# XOR_GATE.net
KiCad netlist of a schematic drawn in Altium Designer
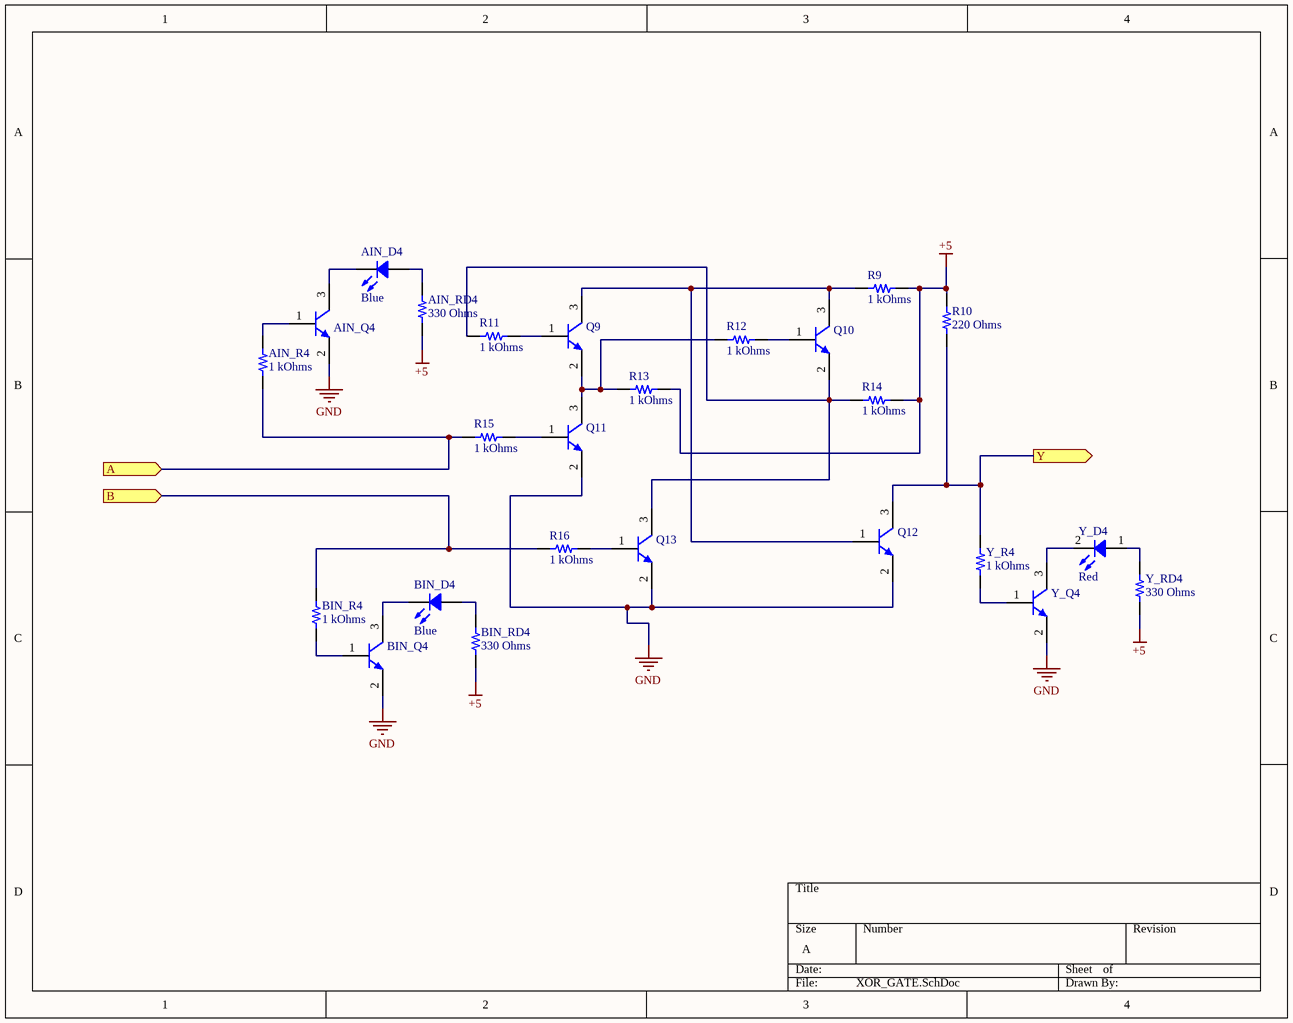
[diagram p0: XOR_GATE.SchDoc]

(export (version "E")
  (design (tool "Eeschema 10.0.6"))
  (components
    (comp (ref "AIN_D4")
      (value "Blue")
      (footprint "LED 0603_1608 BLUE")
      (description "LED BLUE CLEAR 0603 SMD")
      (fields (field (name "PART NUMBER") "IN-S63AT5B") (field (name "MANUFACTURER") "Inolux"))
      (libsource (lib "Celestial Altium Library - altium_library") (part "LED"))
    )
    (comp (ref "AIN_Q4")
      (value "MMSS8050-L-TP")
      (footprint "MCCSEMI SOT-23-3")
      (description "TRANS NPN 25V 1.5A SOT23")
      (fields (field (name "MANUFACTURER") "Micro Commercial Co"))
      (libsource (lib "Celestial Altium Library - altium_library") (part "MCCSEMI NPN SOT-23-3"))
    )
    (comp (ref "AIN_R4")
      (value "1 kOhms")
      (footprint "RES 0603_1608")
      (description "RES SMD 1K OHM 0.1% 1/16W 0603")
      (fields
        (field (name "PART NUMBER") "CPF0603B1K0E")
        (field (name "MANUFACTURER") "TE Connectivity Passive Product")
      )
      (libsource (lib "Celestial Altium Library - altium_library") (part "Resistor"))
    )
    (comp (ref "AIN_RD4")
      (value "330 Ohms")
      (footprint "RES 0603_1608")
      (description "RES 330 OHM 5% 1/10W 0603")
      (fields
        (field (name "PART NUMBER") "RMCF0603JT330R")
        (field (name "MANUFACTURER") "Stackpole Electronics Inc")
      )
      (libsource (lib "Celestial Altium Library - altium_library") (part "Resistor"))
    )
    (comp (ref "BIN_D4")
      (value "Blue")
      (footprint "LED 0603_1608 BLUE")
      (description "LED BLUE CLEAR 0603 SMD")
      (fields (field (name "PART NUMBER") "IN-S63AT5B") (field (name "MANUFACTURER") "Inolux"))
      (libsource (lib "Celestial Altium Library - altium_library") (part "LED"))
    )
    (comp (ref "BIN_Q4")
      (value "MMSS8050-L-TP")
      (footprint "MCCSEMI SOT-23-3")
      (description "TRANS NPN 25V 1.5A SOT23")
      (fields (field (name "MANUFACTURER") "Micro Commercial Co"))
      (libsource (lib "Celestial Altium Library - altium_library") (part "MCCSEMI NPN SOT-23-3"))
    )
    (comp (ref "BIN_R4")
      (value "1 kOhms")
      (footprint "RES 0603_1608")
      (description "RES SMD 1K OHM 0.1% 1/16W 0603")
      (fields
        (field (name "PART NUMBER") "CPF0603B1K0E")
        (field (name "MANUFACTURER") "TE Connectivity Passive Product")
      )
      (libsource (lib "Celestial Altium Library - altium_library") (part "Resistor"))
    )
    (comp (ref "BIN_RD4")
      (value "330 Ohms")
      (footprint "RES 0603_1608")
      (description "RES 330 OHM 5% 1/10W 0603")
      (fields
        (field (name "PART NUMBER") "RMCF0603JT330R")
        (field (name "MANUFACTURER") "Stackpole Electronics Inc")
      )
      (libsource (lib "Celestial Altium Library - altium_library") (part "Resistor"))
    )
    (comp (ref "Q9")
      (value "MMSS8050-L-TP")
      (footprint "MCCSEMI SOT-23-3")
      (description "TRANS NPN 25V 1.5A SOT23")
      (fields (field (name "MANUFACTURER") "Micro Commercial Co"))
      (libsource (lib "Celestial Altium Library - altium_library") (part "MCCSEMI NPN SOT-23-3"))
    )
    (comp (ref "Q10")
      (value "MMSS8050-L-TP")
      (footprint "MCCSEMI SOT-23-3")
      (description "TRANS NPN 25V 1.5A SOT23")
      (fields (field (name "MANUFACTURER") "Micro Commercial Co"))
      (libsource (lib "Celestial Altium Library - altium_library") (part "MCCSEMI NPN SOT-23-3"))
    )
    (comp (ref "Q11")
      (value "MMSS8050-L-TP")
      (footprint "MCCSEMI SOT-23-3")
      (description "TRANS NPN 25V 1.5A SOT23")
      (fields (field (name "MANUFACTURER") "Micro Commercial Co"))
      (libsource (lib "Celestial Altium Library - altium_library") (part "MCCSEMI NPN SOT-23-3"))
    )
    (comp (ref "Q12")
      (value "MMSS8050-L-TP")
      (footprint "MCCSEMI SOT-23-3")
      (description "TRANS NPN 25V 1.5A SOT23")
      (fields (field (name "MANUFACTURER") "Micro Commercial Co"))
      (libsource (lib "Celestial Altium Library - altium_library") (part "MCCSEMI NPN SOT-23-3"))
    )
    (comp (ref "Q13")
      (value "MMSS8050-L-TP")
      (footprint "MCCSEMI SOT-23-3")
      (description "TRANS NPN 25V 1.5A SOT23")
      (fields (field (name "MANUFACTURER") "Micro Commercial Co"))
      (libsource (lib "Celestial Altium Library - altium_library") (part "MCCSEMI NPN SOT-23-3"))
    )
    (comp (ref "R9")
      (value "1 kOhms")
      (footprint "RES 0603_1608")
      (description "RES SMD 1K OHM 0.1% 1/16W 0603")
      (fields
        (field (name "PART NUMBER") "CPF0603B1K0E")
        (field (name "MANUFACTURER") "TE Connectivity Passive Product")
      )
      (libsource (lib "Celestial Altium Library - altium_library") (part "Resistor"))
    )
    (comp (ref "R10")
      (value "220 Ohms")
      (footprint "RES 0603_1608")
      (description "RES SMD 220 OHM 0.5% 1/10W 0603")
      (fields
        (field (name "PART NUMBER") "ERA-3AED221V")
        (field (name "MANUFACTURER") "Panasonic Electronic Components")
      )
      (libsource (lib "Celestial Altium Library - altium_library") (part "Resistor"))
    )
    (comp (ref "R11")
      (value "1 kOhms")
      (footprint "RES 0603_1608")
      (description "RES SMD 1K OHM 0.1% 1/16W 0603")
      (fields
        (field (name "PART NUMBER") "CPF0603B1K0E")
        (field (name "MANUFACTURER") "TE Connectivity Passive Product")
      )
      (libsource (lib "Celestial Altium Library - altium_library") (part "Resistor"))
    )
    (comp (ref "R12")
      (value "1 kOhms")
      (footprint "RES 0603_1608")
      (description "RES SMD 1K OHM 0.1% 1/16W 0603")
      (fields
        (field (name "PART NUMBER") "CPF0603B1K0E")
        (field (name "MANUFACTURER") "TE Connectivity Passive Product")
      )
      (libsource (lib "Celestial Altium Library - altium_library") (part "Resistor"))
    )
    (comp (ref "R13")
      (value "1 kOhms")
      (footprint "RES 0603_1608")
      (description "RES SMD 1K OHM 0.1% 1/16W 0603")
      (fields
        (field (name "PART NUMBER") "CPF0603B1K0E")
        (field (name "MANUFACTURER") "TE Connectivity Passive Product")
      )
      (libsource (lib "Celestial Altium Library - altium_library") (part "Resistor"))
    )
    (comp (ref "R14")
      (value "1 kOhms")
      (footprint "RES 0603_1608")
      (description "RES SMD 1K OHM 0.1% 1/16W 0603")
      (fields
        (field (name "PART NUMBER") "CPF0603B1K0E")
        (field (name "MANUFACTURER") "TE Connectivity Passive Product")
      )
      (libsource (lib "Celestial Altium Library - altium_library") (part "Resistor"))
    )
    (comp (ref "R15")
      (value "1 kOhms")
      (footprint "RES 0603_1608")
      (description "RES SMD 1K OHM 0.1% 1/16W 0603")
      (fields
        (field (name "PART NUMBER") "CPF0603B1K0E")
        (field (name "MANUFACTURER") "TE Connectivity Passive Product")
      )
      (libsource (lib "Celestial Altium Library - altium_library") (part "Resistor"))
    )
    (comp (ref "R16")
      (value "1 kOhms")
      (footprint "RES 0603_1608")
      (description "RES SMD 1K OHM 0.1% 1/16W 0603")
      (fields
        (field (name "PART NUMBER") "CPF0603B1K0E")
        (field (name "MANUFACTURER") "TE Connectivity Passive Product")
      )
      (libsource (lib "Celestial Altium Library - altium_library") (part "Resistor"))
    )
    (comp (ref "Y_D4")
      (value "Red")
      (footprint "LED 0603_1608 RED")
      (description "LED RED CLEAR CHIP SMD")
      (fields (field (name "PART NUMBER") "XZMDK53W-8") (field (name "MANUFACTURER") "SunLED"))
      (libsource (lib "") (part "LED_1"))
    )
    (comp (ref "Y_Q4")
      (value "MMSS8050-L-TP")
      (footprint "MCCSEMI SOT-23-3")
      (description "TRANS NPN 25V 1.5A SOT23")
      (fields (field (name "MANUFACTURER") "Micro Commercial Co"))
      (libsource (lib "Celestial Altium Library - altium_library") (part "MCCSEMI NPN SOT-23-3"))
    )
    (comp (ref "Y_R4")
      (value "1 kOhms")
      (footprint "RES 0603_1608")
      (description "RES SMD 1K OHM 0.1% 1/16W 0603")
      (fields
        (field (name "PART NUMBER") "CPF0603B1K0E")
        (field (name "MANUFACTURER") "TE Connectivity Passive Product")
      )
      (libsource (lib "Celestial Altium Library - altium_library") (part "Resistor"))
    )
    (comp (ref "Y_RD4")
      (value "330 Ohms")
      (footprint "RES 0603_1608")
      (description "RES 330 OHM 5% 1/10W 0603")
      (fields
        (field (name "PART NUMBER") "RMCF0603JT330R")
        (field (name "MANUFACTURER") "Stackpole Electronics Inc")
      )
      (libsource (lib "Celestial Altium Library - altium_library") (part "Resistor"))
    )
  )
  (nets
    (net (code "1") (name "+5") (class "Default")
      (node (ref "AIN_RD4") (pin "1") (pinfunction "1_1") (pintype "passive"))
      (node (ref "BIN_RD4") (pin "1") (pinfunction "1_1") (pintype "passive"))
      (node (ref "R10") (pin "2") (pinfunction "2_2") (pintype "passive"))
      (node (ref "R13") (pin "2") (pinfunction "2_2") (pintype "passive"))
      (node (ref "R14") (pin "2") (pinfunction "2_2") (pintype "passive"))
      (node (ref "R9") (pin "2") (pinfunction "2_2") (pintype "passive"))
      (node (ref "Y_RD4") (pin "1") (pinfunction "1_1") (pintype "passive"))
    )
    (net (code "2") (name "/A") (class "Default")
      (node (ref "AIN_R4") (pin "2") (pinfunction "2_2") (pintype "passive"))
      (node (ref "R15") (pin "1") (pinfunction "1_1") (pintype "passive"))
    )
    (net (code "3") (name "/B") (class "Default")
      (node (ref "BIN_R4") (pin "2") (pinfunction "2_2") (pintype "passive"))
      (node (ref "R16") (pin "1") (pinfunction "1_1") (pintype "passive"))
    )
    (net (code "4") (name "/Y") (class "Default")
      (node (ref "Q12") (pin "3") (pinfunction "C_3") (pintype "passive"))
      (node (ref "R10") (pin "1") (pinfunction "1_1") (pintype "passive"))
      (node (ref "Y_R4") (pin "2") (pinfunction "2_2") (pintype "passive"))
    )
    (net (code "5") (name "GND") (class "Default")
      (node (ref "AIN_Q4") (pin "2") (pinfunction "E_2") (pintype "passive"))
      (node (ref "BIN_Q4") (pin "2") (pinfunction "E_2") (pintype "passive"))
      (node (ref "Q11") (pin "2") (pinfunction "E_2") (pintype "passive"))
      (node (ref "Q12") (pin "2") (pinfunction "E_2") (pintype "passive"))
      (node (ref "Q13") (pin "2") (pinfunction "E_2") (pintype "passive"))
      (node (ref "Y_Q4") (pin "2") (pinfunction "E_2") (pintype "passive"))
    )
    (net (code "6") (name "Net-(AIN_D4-Pad1)") (class "Default")
      (node (ref "AIN_D4") (pin "1") (pinfunction "1_1") (pintype "passive"))
      (node (ref "AIN_RD4") (pin "2") (pinfunction "2_2") (pintype "passive"))
    )
    (net (code "7") (name "Net-(AIN_Q4-B)") (class "Default")
      (node (ref "AIN_Q4") (pin "1") (pinfunction "B_1") (pintype "passive"))
      (node (ref "AIN_R4") (pin "1") (pinfunction "1_1") (pintype "passive"))
    )
    (net (code "8") (name "Net-(AIN_Q4-C)") (class "Default")
      (node (ref "AIN_D4") (pin "2") (pinfunction "2_2") (pintype "passive"))
      (node (ref "AIN_Q4") (pin "3") (pinfunction "C_3") (pintype "passive"))
    )
    (net (code "9") (name "Net-(BIN_D4-Pad1)") (class "Default")
      (node (ref "BIN_D4") (pin "1") (pinfunction "1_1") (pintype "passive"))
      (node (ref "BIN_RD4") (pin "2") (pinfunction "2_2") (pintype "passive"))
    )
    (net (code "10") (name "Net-(BIN_Q4-B)") (class "Default")
      (node (ref "BIN_Q4") (pin "1") (pinfunction "B_1") (pintype "passive"))
      (node (ref "BIN_R4") (pin "1") (pinfunction "1_1") (pintype "passive"))
    )
    (net (code "11") (name "Net-(BIN_Q4-C)") (class "Default")
      (node (ref "BIN_D4") (pin "2") (pinfunction "2_2") (pintype "passive"))
      (node (ref "BIN_Q4") (pin "3") (pinfunction "C_3") (pintype "passive"))
    )
    (net (code "12") (name "Net-(Q9-B)") (class "Default")
      (node (ref "Q9") (pin "1") (pinfunction "B_1") (pintype "passive"))
      (node (ref "R11") (pin "2") (pinfunction "2_2") (pintype "passive"))
    )
    (net (code "13") (name "Net-(Q10-B)") (class "Default")
      (node (ref "Q10") (pin "1") (pinfunction "B_1") (pintype "passive"))
      (node (ref "R12") (pin "2") (pinfunction "2_2") (pintype "passive"))
    )
    (net (code "14") (name "Net-(Q10-C)") (class "Default")
      (node (ref "Q10") (pin "3") (pinfunction "C_3") (pintype "passive"))
      (node (ref "Q12") (pin "1") (pinfunction "B_1") (pintype "passive"))
      (node (ref "Q9") (pin "3") (pinfunction "C_3") (pintype "passive"))
      (node (ref "R9") (pin "1") (pinfunction "1_1") (pintype "passive"))
    )
    (net (code "15") (name "Net-(Q10-E)") (class "Default")
      (node (ref "Q10") (pin "2") (pinfunction "E_2") (pintype "passive"))
      (node (ref "Q13") (pin "3") (pinfunction "C_3") (pintype "passive"))
      (node (ref "R11") (pin "1") (pinfunction "1_1") (pintype "passive"))
      (node (ref "R14") (pin "1") (pinfunction "1_1") (pintype "passive"))
    )
    (net (code "16") (name "Net-(Q11-B)") (class "Default")
      (node (ref "Q11") (pin "1") (pinfunction "B_1") (pintype "passive"))
      (node (ref "R15") (pin "2") (pinfunction "2_2") (pintype "passive"))
    )
    (net (code "17") (name "Net-(Q11-C)") (class "Default")
      (node (ref "Q11") (pin "3") (pinfunction "C_3") (pintype "passive"))
      (node (ref "Q9") (pin "2") (pinfunction "E_2") (pintype "passive"))
      (node (ref "R12") (pin "1") (pinfunction "1_1") (pintype "passive"))
      (node (ref "R13") (pin "1") (pinfunction "1_1") (pintype "passive"))
    )
    (net (code "18") (name "Net-(Q13-B)") (class "Default")
      (node (ref "Q13") (pin "1") (pinfunction "B_1") (pintype "passive"))
      (node (ref "R16") (pin "2") (pinfunction "2_2") (pintype "passive"))
    )
    (net (code "19") (name "Net-(Y_D4-Pad1)") (class "Default")
      (node (ref "Y_D4") (pin "1") (pinfunction "1_1") (pintype "passive"))
      (node (ref "Y_RD4") (pin "2") (pinfunction "2_2") (pintype "passive"))
    )
    (net (code "20") (name "Net-(Y_Q4-B)") (class "Default")
      (node (ref "Y_Q4") (pin "1") (pinfunction "B_1") (pintype "passive"))
      (node (ref "Y_R4") (pin "1") (pinfunction "1_1") (pintype "passive"))
    )
    (net (code "21") (name "Net-(Y_Q4-C)") (class "Default")
      (node (ref "Y_D4") (pin "2") (pinfunction "2_2") (pintype "passive"))
      (node (ref "Y_Q4") (pin "3") (pinfunction "C_3") (pintype "passive"))
    )
  )
)
